# H01.net
KiCad netlist of a schematic drawn in EAGLE
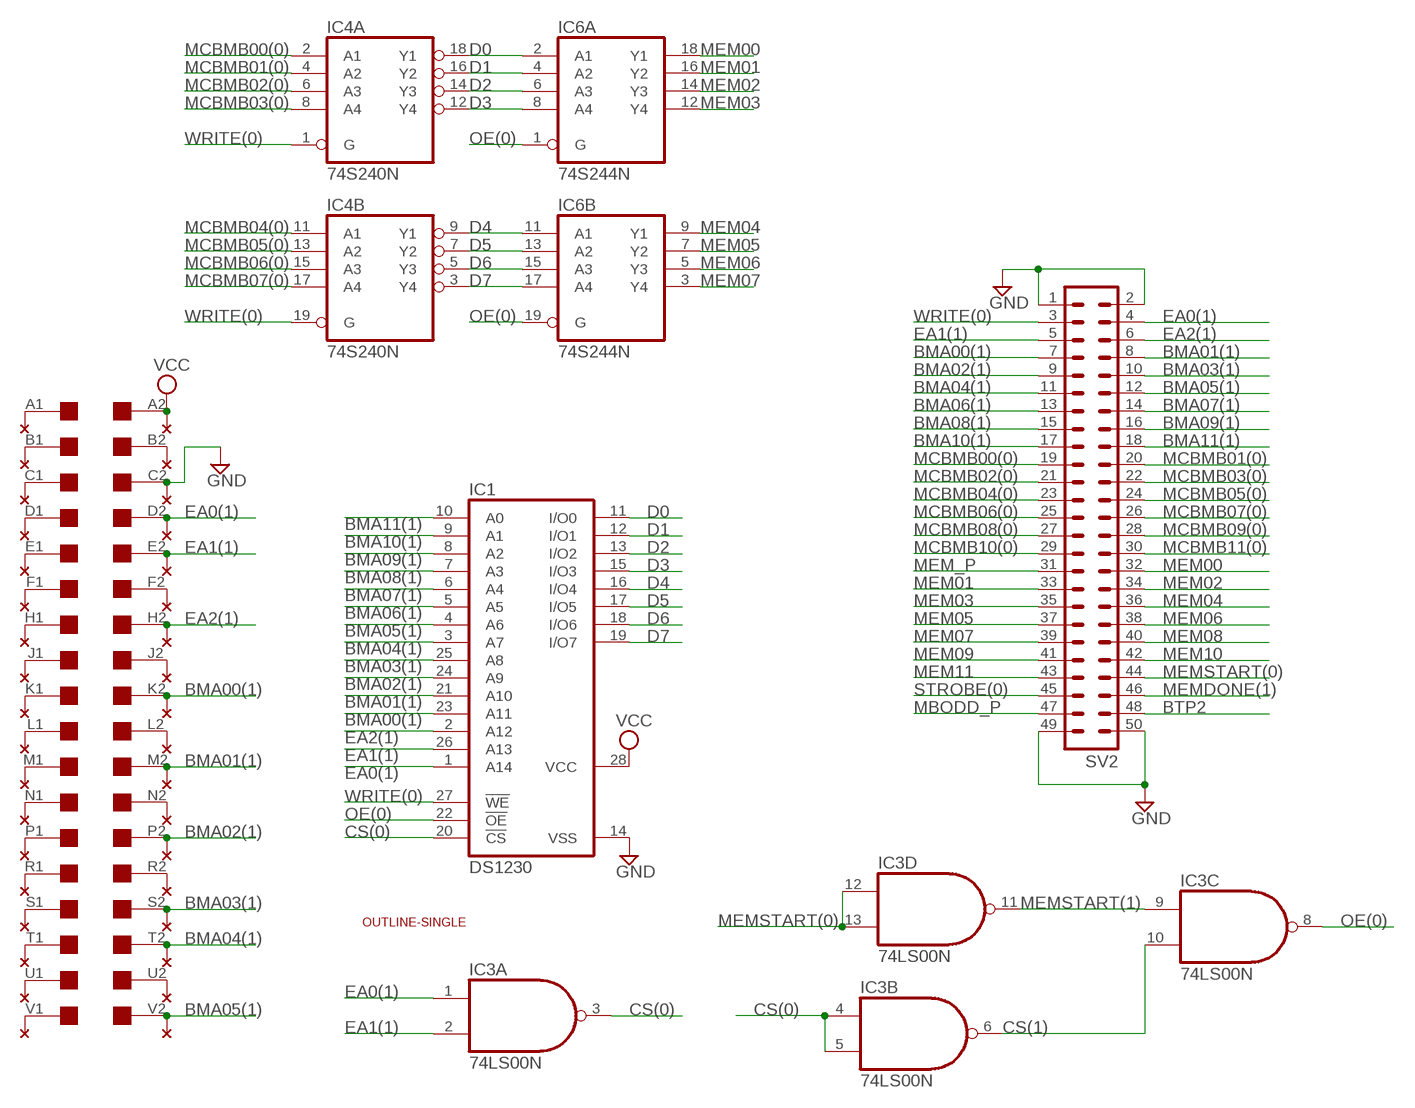
[diagram p0: schematic, sheet 1]

(export (version "E")
  (design (tool "Eeschema 10.0.6"))
  (components
    (comp (ref "EDGE1")
      (value "EDGE-2CONNECTOR")
      (footprint "eagle-import:EDGE-CON2")
      (libsource (lib "eagle-import") (part "EDGE-2CONNECTOR"))
    )
    (comp (ref "IC1")
      (value "DS1230")
      (footprint "eagle-import:DIL28-6")
      (libsource (lib "eagle-import") (part "62256P"))
    )
    (comp (ref "IC3")
      (value "74LS00N")
      (footprint "eagle-import:DIL14")
      (libsource (lib "eagle-import") (part "7400NLS"))
    )
    (comp (ref "IC4")
      (value "74S240N")
      (footprint "eagle-import:DIL20")
      (libsource (lib "eagle-import") (part "74240NS"))
    )
    (comp (ref "IC6")
      (value "74S244N")
      (footprint "eagle-import:DIL20")
      (libsource (lib "eagle-import") (part "74244NS"))
    )
    (comp (ref "SV2")
      (value "ML50L")
      (footprint "eagle-import:ML50L")
      (libsource (lib "eagle-import") (part "ML50L"))
    )
    (comp (ref "U$2")
      (value "OUTLINE-SINGLE")
      (footprint "eagle-import:SINGLE")
      (libsource (lib "eagle-import") (part "OUTLINE-SINGLE"))
    )
    (comp (ref "U$3")
      (value "THRU-HOLE2")
      (footprint "eagle-import:THRU-HOLEB")
      (libsource (lib "eagle-import") (part "THRU-HOLE2"))
    )
  )
  (nets
    (net (code "1") (name "/BMA00(1)") (class "Default")
      (node (ref "EDGE1") (pin "K2") (pinfunction "1_K2") (pintype "bidirectional"))
      (node (ref "IC1") (pin "23") (pinfunction "A11_23") (pintype "input"))
      (node (ref "SV2") (pin "7") (pinfunction "7_7") (pintype "passive"))
      (node (ref "U$3") (pin "K2") (pinfunction "P$1_K2") (pintype "passive"))
    )
    (net (code "2") (name "/BMA01(1)") (class "Default")
      (node (ref "EDGE1") (pin "M2") (pinfunction "1_M2") (pintype "bidirectional"))
      (node (ref "IC1") (pin "21") (pinfunction "A10_21") (pintype "input"))
      (node (ref "SV2") (pin "8") (pinfunction "8_8") (pintype "passive"))
      (node (ref "U$3") (pin "M2") (pinfunction "P$1_M2") (pintype "passive"))
    )
    (net (code "3") (name "/BMA02(1)") (class "Default")
      (node (ref "EDGE1") (pin "P2") (pinfunction "1_P2") (pintype "bidirectional"))
      (node (ref "IC1") (pin "24") (pinfunction "A9_24") (pintype "input"))
      (node (ref "SV2") (pin "9") (pinfunction "9_9") (pintype "passive"))
      (node (ref "U$3") (pin "P2") (pinfunction "P$1_P2") (pintype "passive"))
    )
    (net (code "4") (name "/BMA03(1)") (class "Default")
      (node (ref "EDGE1") (pin "S2") (pinfunction "1_S2") (pintype "bidirectional"))
      (node (ref "IC1") (pin "25") (pinfunction "A8_25") (pintype "input"))
      (node (ref "SV2") (pin "10") (pinfunction "10_10") (pintype "passive"))
      (node (ref "U$3") (pin "S2") (pinfunction "P$1_S2") (pintype "passive"))
    )
    (net (code "5") (name "/BMA04(1)") (class "Default")
      (node (ref "EDGE1") (pin "T2") (pinfunction "1_T2") (pintype "bidirectional"))
      (node (ref "IC1") (pin "3") (pinfunction "A7_3") (pintype "input"))
      (node (ref "SV2") (pin "11") (pinfunction "11_11") (pintype "passive"))
      (node (ref "U$3") (pin "T2") (pinfunction "P$1_T2") (pintype "passive"))
    )
    (net (code "6") (name "/BMA05(1)") (class "Default")
      (node (ref "EDGE1") (pin "V2") (pinfunction "1_V2") (pintype "bidirectional"))
      (node (ref "IC1") (pin "4") (pinfunction "A6_4") (pintype "input"))
      (node (ref "SV2") (pin "12") (pinfunction "12_12") (pintype "passive"))
      (node (ref "U$3") (pin "V2") (pinfunction "P$1_V2") (pintype "passive"))
    )
    (net (code "7") (name "/BMA06(1)") (class "Default")
      (node (ref "IC1") (pin "5") (pinfunction "A5_5") (pintype "input"))
      (node (ref "SV2") (pin "13") (pinfunction "13_13") (pintype "passive"))
    )
    (net (code "8") (name "/BMA07(1)") (class "Default")
      (node (ref "IC1") (pin "6") (pinfunction "A4_6") (pintype "input"))
      (node (ref "SV2") (pin "14") (pinfunction "14_14") (pintype "passive"))
    )
    (net (code "9") (name "/BMA08(1)") (class "Default")
      (node (ref "IC1") (pin "7") (pinfunction "A3_7") (pintype "input"))
      (node (ref "SV2") (pin "15") (pinfunction "15_15") (pintype "passive"))
    )
    (net (code "10") (name "/BMA09(1)") (class "Default")
      (node (ref "IC1") (pin "8") (pinfunction "A2_8") (pintype "input"))
      (node (ref "SV2") (pin "16") (pinfunction "16_16") (pintype "passive"))
    )
    (net (code "11") (name "/BMA10(1)") (class "Default")
      (node (ref "IC1") (pin "9") (pinfunction "A1_9") (pintype "input"))
      (node (ref "SV2") (pin "17") (pinfunction "17_17") (pintype "passive"))
    )
    (net (code "12") (name "/BMA11(1)") (class "Default")
      (node (ref "IC1") (pin "10") (pinfunction "A0_10") (pintype "input"))
      (node (ref "SV2") (pin "18") (pinfunction "18_18") (pintype "passive"))
    )
    (net (code "13") (name "/BTP2") (class "Default")
      (node (ref "SV2") (pin "48") (pinfunction "48_48") (pintype "passive"))
    )
    (net (code "14") (name "/CS(0)") (class "Default")
      (node (ref "IC1") (pin "20") (pinfunction "~{CS}_20") (pintype "input"))
      (node (ref "IC3") (pin "3") (pinfunction "O_3") (pintype "output"))
      (node (ref "IC3") (pin "4") (pinfunction "I0_4") (pintype "input"))
      (node (ref "IC3") (pin "5") (pinfunction "I1_5") (pintype "input"))
    )
    (net (code "15") (name "/CS(1)") (class "Default")
      (node (ref "IC3") (pin "10") (pinfunction "I1_10") (pintype "input"))
      (node (ref "IC3") (pin "6") (pinfunction "O_6") (pintype "output"))
    )
    (net (code "16") (name "/D0") (class "Default")
      (node (ref "IC1") (pin "11") (pinfunction "I/O0_11") (pintype "bidirectional"))
      (node (ref "IC4") (pin "18") (pinfunction "Y1_18") (pintype "tri_state"))
      (node (ref "IC6") (pin "2") (pinfunction "A1_2") (pintype "input"))
    )
    (net (code "17") (name "/D1") (class "Default")
      (node (ref "IC1") (pin "12") (pinfunction "I/O1_12") (pintype "bidirectional"))
      (node (ref "IC4") (pin "16") (pinfunction "Y2_16") (pintype "tri_state"))
      (node (ref "IC6") (pin "4") (pinfunction "A2_4") (pintype "input"))
    )
    (net (code "18") (name "/D2") (class "Default")
      (node (ref "IC1") (pin "13") (pinfunction "I/O2_13") (pintype "bidirectional"))
      (node (ref "IC4") (pin "14") (pinfunction "Y3_14") (pintype "tri_state"))
      (node (ref "IC6") (pin "6") (pinfunction "A3_6") (pintype "input"))
    )
    (net (code "19") (name "/D3") (class "Default")
      (node (ref "IC1") (pin "15") (pinfunction "I/O3_15") (pintype "bidirectional"))
      (node (ref "IC4") (pin "12") (pinfunction "Y4_12") (pintype "tri_state"))
      (node (ref "IC6") (pin "8") (pinfunction "A4_8") (pintype "input"))
    )
    (net (code "20") (name "/D4") (class "Default")
      (node (ref "IC1") (pin "16") (pinfunction "I/O4_16") (pintype "bidirectional"))
      (node (ref "IC4") (pin "9") (pinfunction "Y1_9") (pintype "tri_state"))
      (node (ref "IC6") (pin "11") (pinfunction "A1_11") (pintype "input"))
    )
    (net (code "21") (name "/D5") (class "Default")
      (node (ref "IC1") (pin "17") (pinfunction "I/O5_17") (pintype "bidirectional"))
      (node (ref "IC4") (pin "7") (pinfunction "Y2_7") (pintype "tri_state"))
      (node (ref "IC6") (pin "13") (pinfunction "A2_13") (pintype "input"))
    )
    (net (code "22") (name "/D6") (class "Default")
      (node (ref "IC1") (pin "18") (pinfunction "I/O6_18") (pintype "bidirectional"))
      (node (ref "IC4") (pin "5") (pinfunction "Y3_5") (pintype "tri_state"))
      (node (ref "IC6") (pin "15") (pinfunction "A3_15") (pintype "input"))
    )
    (net (code "23") (name "/D7") (class "Default")
      (node (ref "IC1") (pin "19") (pinfunction "I/O7_19") (pintype "bidirectional"))
      (node (ref "IC4") (pin "3") (pinfunction "Y4_3") (pintype "tri_state"))
      (node (ref "IC6") (pin "17") (pinfunction "A4_17") (pintype "input"))
    )
    (net (code "24") (name "/EA0(1)") (class "Default")
      (node (ref "EDGE1") (pin "D2") (pinfunction "1_D2") (pintype "bidirectional"))
      (node (ref "IC1") (pin "1") (pinfunction "A14_1") (pintype "input"))
      (node (ref "IC3") (pin "1") (pinfunction "I0_1") (pintype "input"))
      (node (ref "SV2") (pin "4") (pinfunction "4_4") (pintype "passive"))
      (node (ref "U$3") (pin "D2") (pinfunction "P$1_D2") (pintype "passive"))
    )
    (net (code "25") (name "/EA1(1)") (class "Default")
      (node (ref "EDGE1") (pin "E2") (pinfunction "1_E2") (pintype "bidirectional"))
      (node (ref "IC1") (pin "26") (pinfunction "A13_26") (pintype "input"))
      (node (ref "IC3") (pin "2") (pinfunction "I1_2") (pintype "input"))
      (node (ref "SV2") (pin "5") (pinfunction "5_5") (pintype "passive"))
      (node (ref "U$3") (pin "E2") (pinfunction "P$1_E2") (pintype "passive"))
    )
    (net (code "26") (name "/EA2(1)") (class "Default")
      (node (ref "EDGE1") (pin "H2") (pinfunction "1_H2") (pintype "bidirectional"))
      (node (ref "IC1") (pin "2") (pinfunction "A12_2") (pintype "input"))
      (node (ref "SV2") (pin "6") (pinfunction "6_6") (pintype "passive"))
      (node (ref "U$3") (pin "H2") (pinfunction "P$1_H2") (pintype "passive"))
    )
    (net (code "27") (name "/MBODD_P") (class "Default")
      (node (ref "SV2") (pin "47") (pinfunction "47_47") (pintype "passive"))
    )
    (net (code "28") (name "/MCBMB00(0)") (class "Default")
      (node (ref "IC4") (pin "2") (pinfunction "A1_2") (pintype "input"))
      (node (ref "SV2") (pin "19") (pinfunction "19_19") (pintype "passive"))
    )
    (net (code "29") (name "/MCBMB01(0)") (class "Default")
      (node (ref "IC4") (pin "4") (pinfunction "A2_4") (pintype "input"))
      (node (ref "SV2") (pin "20") (pinfunction "20_20") (pintype "passive"))
    )
    (net (code "30") (name "/MCBMB02(0)") (class "Default")
      (node (ref "IC4") (pin "6") (pinfunction "A3_6") (pintype "input"))
      (node (ref "SV2") (pin "21") (pinfunction "21_21") (pintype "passive"))
    )
    (net (code "31") (name "/MCBMB03(0)") (class "Default")
      (node (ref "IC4") (pin "8") (pinfunction "A4_8") (pintype "input"))
      (node (ref "SV2") (pin "22") (pinfunction "22_22") (pintype "passive"))
    )
    (net (code "32") (name "/MCBMB04(0)") (class "Default")
      (node (ref "IC4") (pin "11") (pinfunction "A1_11") (pintype "input"))
      (node (ref "SV2") (pin "23") (pinfunction "23_23") (pintype "passive"))
    )
    (net (code "33") (name "/MCBMB05(0)") (class "Default")
      (node (ref "IC4") (pin "13") (pinfunction "A2_13") (pintype "input"))
      (node (ref "SV2") (pin "24") (pinfunction "24_24") (pintype "passive"))
    )
    (net (code "34") (name "/MCBMB06(0)") (class "Default")
      (node (ref "IC4") (pin "15") (pinfunction "A3_15") (pintype "input"))
      (node (ref "SV2") (pin "25") (pinfunction "25_25") (pintype "passive"))
    )
    (net (code "35") (name "/MCBMB07(0)") (class "Default")
      (node (ref "IC4") (pin "17") (pinfunction "A4_17") (pintype "input"))
      (node (ref "SV2") (pin "26") (pinfunction "26_26") (pintype "passive"))
    )
    (net (code "36") (name "/MCBMB08(0)") (class "Default")
      (node (ref "SV2") (pin "27") (pinfunction "27_27") (pintype "passive"))
    )
    (net (code "37") (name "/MCBMB09(0)") (class "Default")
      (node (ref "SV2") (pin "28") (pinfunction "28_28") (pintype "passive"))
    )
    (net (code "38") (name "/MCBMB10(0)") (class "Default")
      (node (ref "SV2") (pin "29") (pinfunction "29_29") (pintype "passive"))
    )
    (net (code "39") (name "/MCBMB11(0)") (class "Default")
      (node (ref "SV2") (pin "30") (pinfunction "30_30") (pintype "passive"))
    )
    (net (code "40") (name "/MEM00") (class "Default")
      (node (ref "IC6") (pin "18") (pinfunction "Y1_18") (pintype "tri_state"))
      (node (ref "SV2") (pin "32") (pinfunction "32_32") (pintype "passive"))
    )
    (net (code "41") (name "/MEM01") (class "Default")
      (node (ref "IC6") (pin "16") (pinfunction "Y2_16") (pintype "tri_state"))
      (node (ref "SV2") (pin "33") (pinfunction "33_33") (pintype "passive"))
    )
    (net (code "42") (name "/MEM02") (class "Default")
      (node (ref "IC6") (pin "14") (pinfunction "Y3_14") (pintype "tri_state"))
      (node (ref "SV2") (pin "34") (pinfunction "34_34") (pintype "passive"))
    )
    (net (code "43") (name "/MEM03") (class "Default")
      (node (ref "IC6") (pin "12") (pinfunction "Y4_12") (pintype "tri_state"))
      (node (ref "SV2") (pin "35") (pinfunction "35_35") (pintype "passive"))
    )
    (net (code "44") (name "/MEM04") (class "Default")
      (node (ref "IC6") (pin "9") (pinfunction "Y1_9") (pintype "tri_state"))
      (node (ref "SV2") (pin "36") (pinfunction "36_36") (pintype "passive"))
    )
    (net (code "45") (name "/MEM05") (class "Default")
      (node (ref "IC6") (pin "7") (pinfunction "Y2_7") (pintype "tri_state"))
      (node (ref "SV2") (pin "37") (pinfunction "37_37") (pintype "passive"))
    )
    (net (code "46") (name "/MEM06") (class "Default")
      (node (ref "IC6") (pin "5") (pinfunction "Y3_5") (pintype "tri_state"))
      (node (ref "SV2") (pin "38") (pinfunction "38_38") (pintype "passive"))
    )
    (net (code "47") (name "/MEM07") (class "Default")
      (node (ref "IC6") (pin "3") (pinfunction "Y4_3") (pintype "tri_state"))
      (node (ref "SV2") (pin "39") (pinfunction "39_39") (pintype "passive"))
    )
    (net (code "48") (name "/MEM08") (class "Default")
      (node (ref "SV2") (pin "40") (pinfunction "40_40") (pintype "passive"))
    )
    (net (code "49") (name "/MEM09") (class "Default")
      (node (ref "SV2") (pin "41") (pinfunction "41_41") (pintype "passive"))
    )
    (net (code "50") (name "/MEM10") (class "Default")
      (node (ref "SV2") (pin "42") (pinfunction "42_42") (pintype "passive"))
    )
    (net (code "51") (name "/MEM11") (class "Default")
      (node (ref "SV2") (pin "43") (pinfunction "43_43") (pintype "passive"))
    )
    (net (code "52") (name "/MEMDONE(1)") (class "Default")
      (node (ref "SV2") (pin "46") (pinfunction "46_46") (pintype "passive"))
    )
    (net (code "53") (name "/MEMSTART(0)") (class "Default")
      (node (ref "IC3") (pin "12") (pinfunction "I0_12") (pintype "input"))
      (node (ref "IC3") (pin "13") (pinfunction "I1_13") (pintype "input"))
      (node (ref "SV2") (pin "44") (pinfunction "44_44") (pintype "passive"))
    )
    (net (code "54") (name "/MEMSTART(1)") (class "Default")
      (node (ref "IC3") (pin "11") (pinfunction "O_11") (pintype "output"))
      (node (ref "IC3") (pin "9") (pinfunction "I0_9") (pintype "input"))
    )
    (net (code "55") (name "/MEM_P") (class "Default")
      (node (ref "SV2") (pin "31") (pinfunction "31_31") (pintype "passive"))
    )
    (net (code "56") (name "/OE(0)") (class "Default")
      (node (ref "IC1") (pin "22") (pinfunction "~{OE}_22") (pintype "input"))
      (node (ref "IC3") (pin "8") (pinfunction "O_8") (pintype "output"))
      (node (ref "IC6") (pin "1") (pinfunction "G_1") (pintype "input"))
      (node (ref "IC6") (pin "19") (pinfunction "G_19") (pintype "input"))
    )
    (net (code "57") (name "/STROBE(0)") (class "Default")
      (node (ref "SV2") (pin "45") (pinfunction "45_45") (pintype "passive"))
    )
    (net (code "58") (name "/WRITE(0)") (class "Default")
      (node (ref "IC1") (pin "27") (pinfunction "~{WE}_27") (pintype "input"))
      (node (ref "IC4") (pin "1") (pinfunction "G_1") (pintype "input"))
      (node (ref "IC4") (pin "19") (pinfunction "G_19") (pintype "input"))
      (node (ref "SV2") (pin "3") (pinfunction "3_3") (pintype "passive"))
    )
    (net (code "59") (name "GND") (class "Default")
      (node (ref "EDGE1") (pin "C2") (pinfunction "1_C2") (pintype "bidirectional"))
      (node (ref "IC1") (pin "14") (pinfunction "VSS_14") (pintype "power_in"))
      (node (ref "SV2") (pin "1") (pinfunction "1_1") (pintype "passive"))
      (node (ref "SV2") (pin "2") (pinfunction "2_2") (pintype "passive"))
      (node (ref "SV2") (pin "49") (pinfunction "49_49") (pintype "passive"))
      (node (ref "SV2") (pin "50") (pinfunction "50_50") (pintype "passive"))
      (node (ref "U$3") (pin "C2") (pinfunction "P$1_C2") (pintype "passive"))
    )
    (net (code "60") (name "Net-(EDGE1A-1)") (class "Default")
      (node (ref "EDGE1") (pin "A1") (pinfunction "1_A1") (pintype "bidirectional"))
      (node (ref "U$3") (pin "A1") (pinfunction "P$1_A1") (pintype "passive"))
    )
    (net (code "61") (name "Net-(EDGE1AA-1)") (class "Default")
      (node (ref "EDGE1") (pin "R1") (pinfunction "1_R1") (pintype "bidirectional"))
      (node (ref "U$3") (pin "R1") (pinfunction "P$1_R1") (pintype "passive"))
    )
    (net (code "62") (name "Net-(EDGE1AB-1)") (class "Default")
      (node (ref "EDGE1") (pin "R2") (pinfunction "1_R2") (pintype "bidirectional"))
      (node (ref "U$3") (pin "R2") (pinfunction "P$1_R2") (pintype "passive"))
    )
    (net (code "63") (name "Net-(EDGE1AC-1)") (class "Default")
      (node (ref "EDGE1") (pin "S1") (pinfunction "1_S1") (pintype "bidirectional"))
      (node (ref "U$3") (pin "S1") (pinfunction "P$1_S1") (pintype "passive"))
    )
    (net (code "64") (name "Net-(EDGE1AE-1)") (class "Default")
      (node (ref "EDGE1") (pin "T1") (pinfunction "1_T1") (pintype "bidirectional"))
      (node (ref "U$3") (pin "T1") (pinfunction "P$1_T1") (pintype "passive"))
    )
    (net (code "65") (name "Net-(EDGE1AG-1)") (class "Default")
      (node (ref "EDGE1") (pin "U1") (pinfunction "1_U1") (pintype "bidirectional"))
      (node (ref "U$3") (pin "U1") (pinfunction "P$1_U1") (pintype "passive"))
    )
    (net (code "66") (name "Net-(EDGE1AH-1)") (class "Default")
      (node (ref "EDGE1") (pin "U2") (pinfunction "1_U2") (pintype "bidirectional"))
      (node (ref "U$3") (pin "U2") (pinfunction "P$1_U2") (pintype "passive"))
    )
    (net (code "67") (name "Net-(EDGE1AI-1)") (class "Default")
      (node (ref "EDGE1") (pin "V1") (pinfunction "1_V1") (pintype "bidirectional"))
      (node (ref "U$3") (pin "V1") (pinfunction "P$1_V1") (pintype "passive"))
    )
    (net (code "68") (name "Net-(EDGE1C-1)") (class "Default")
      (node (ref "EDGE1") (pin "B1") (pinfunction "1_B1") (pintype "bidirectional"))
      (node (ref "U$3") (pin "B1") (pinfunction "P$1_B1") (pintype "passive"))
    )
    (net (code "69") (name "Net-(EDGE1D-1)") (class "Default")
      (node (ref "EDGE1") (pin "B2") (pinfunction "1_B2") (pintype "bidirectional"))
      (node (ref "U$3") (pin "B2") (pinfunction "P$1_B2") (pintype "passive"))
    )
    (net (code "70") (name "Net-(EDGE1E-1)") (class "Default")
      (node (ref "EDGE1") (pin "C1") (pinfunction "1_C1") (pintype "bidirectional"))
      (node (ref "U$3") (pin "C1") (pinfunction "P$1_C1") (pintype "passive"))
    )
    (net (code "71") (name "Net-(EDGE1G-1)") (class "Default")
      (node (ref "EDGE1") (pin "D1") (pinfunction "1_D1") (pintype "bidirectional"))
      (node (ref "U$3") (pin "D1") (pinfunction "P$1_D1") (pintype "passive"))
    )
    (net (code "72") (name "Net-(EDGE1I-1)") (class "Default")
      (node (ref "EDGE1") (pin "E1") (pinfunction "1_E1") (pintype "bidirectional"))
      (node (ref "U$3") (pin "E1") (pinfunction "P$1_E1") (pintype "passive"))
    )
    (net (code "73") (name "Net-(EDGE1K-1)") (class "Default")
      (node (ref "EDGE1") (pin "F1") (pinfunction "1_F1") (pintype "bidirectional"))
      (node (ref "U$3") (pin "F1") (pinfunction "P$1_F1") (pintype "passive"))
    )
    (net (code "74") (name "Net-(EDGE1L-1)") (class "Default")
      (node (ref "EDGE1") (pin "F2") (pinfunction "1_F2") (pintype "bidirectional"))
      (node (ref "U$3") (pin "F2") (pinfunction "P$1_F2") (pintype "passive"))
    )
    (net (code "75") (name "Net-(EDGE1M-1)") (class "Default")
      (node (ref "EDGE1") (pin "H1") (pinfunction "1_H1") (pintype "bidirectional"))
      (node (ref "U$3") (pin "H1") (pinfunction "P$1_H1") (pintype "passive"))
    )
    (net (code "76") (name "Net-(EDGE1O-1)") (class "Default")
      (node (ref "EDGE1") (pin "J1") (pinfunction "1_J1") (pintype "bidirectional"))
      (node (ref "U$3") (pin "J1") (pinfunction "P$1_J1") (pintype "passive"))
    )
    (net (code "77") (name "Net-(EDGE1P-1)") (class "Default")
      (node (ref "EDGE1") (pin "J2") (pinfunction "1_J2") (pintype "bidirectional"))
      (node (ref "U$3") (pin "J2") (pinfunction "P$1_J2") (pintype "passive"))
    )
    (net (code "78") (name "Net-(EDGE1Q-1)") (class "Default")
      (node (ref "EDGE1") (pin "K1") (pinfunction "1_K1") (pintype "bidirectional"))
      (node (ref "U$3") (pin "K1") (pinfunction "P$1_K1") (pintype "passive"))
    )
    (net (code "79") (name "Net-(EDGE1S-1)") (class "Default")
      (node (ref "EDGE1") (pin "L1") (pinfunction "1_L1") (pintype "bidirectional"))
      (node (ref "U$3") (pin "L1") (pinfunction "P$1_L1") (pintype "passive"))
    )
    (net (code "80") (name "Net-(EDGE1T-1)") (class "Default")
      (node (ref "EDGE1") (pin "L2") (pinfunction "1_L2") (pintype "bidirectional"))
      (node (ref "U$3") (pin "L2") (pinfunction "P$1_L2") (pintype "passive"))
    )
    (net (code "81") (name "Net-(EDGE1U-1)") (class "Default")
      (node (ref "EDGE1") (pin "M1") (pinfunction "1_M1") (pintype "bidirectional"))
      (node (ref "U$3") (pin "M1") (pinfunction "P$1_M1") (pintype "passive"))
    )
    (net (code "82") (name "Net-(EDGE1W-1)") (class "Default")
      (node (ref "EDGE1") (pin "N1") (pinfunction "1_N1") (pintype "bidirectional"))
      (node (ref "U$3") (pin "N1") (pinfunction "P$1_N1") (pintype "passive"))
    )
    (net (code "83") (name "Net-(EDGE1X-1)") (class "Default")
      (node (ref "EDGE1") (pin "N2") (pinfunction "1_N2") (pintype "bidirectional"))
      (node (ref "U$3") (pin "N2") (pinfunction "P$1_N2") (pintype "passive"))
    )
    (net (code "84") (name "Net-(EDGE1Y-1)") (class "Default")
      (node (ref "EDGE1") (pin "P1") (pinfunction "1_P1") (pintype "bidirectional"))
      (node (ref "U$3") (pin "P1") (pinfunction "P$1_P1") (pintype "passive"))
    )
    (net (code "85") (name "VCC") (class "Default")
      (node (ref "EDGE1") (pin "A2") (pinfunction "1_A2") (pintype "bidirectional"))
      (node (ref "IC1") (pin "28") (pinfunction "VCC_28") (pintype "power_in"))
      (node (ref "U$3") (pin "A2") (pinfunction "P$1_A2") (pintype "passive"))
    )
  )
)
